# HoneyPI_Platine_2_0_BME680_280_Sensor_Bo.net
KiCad netlist of a schematic drawn in EAGLE
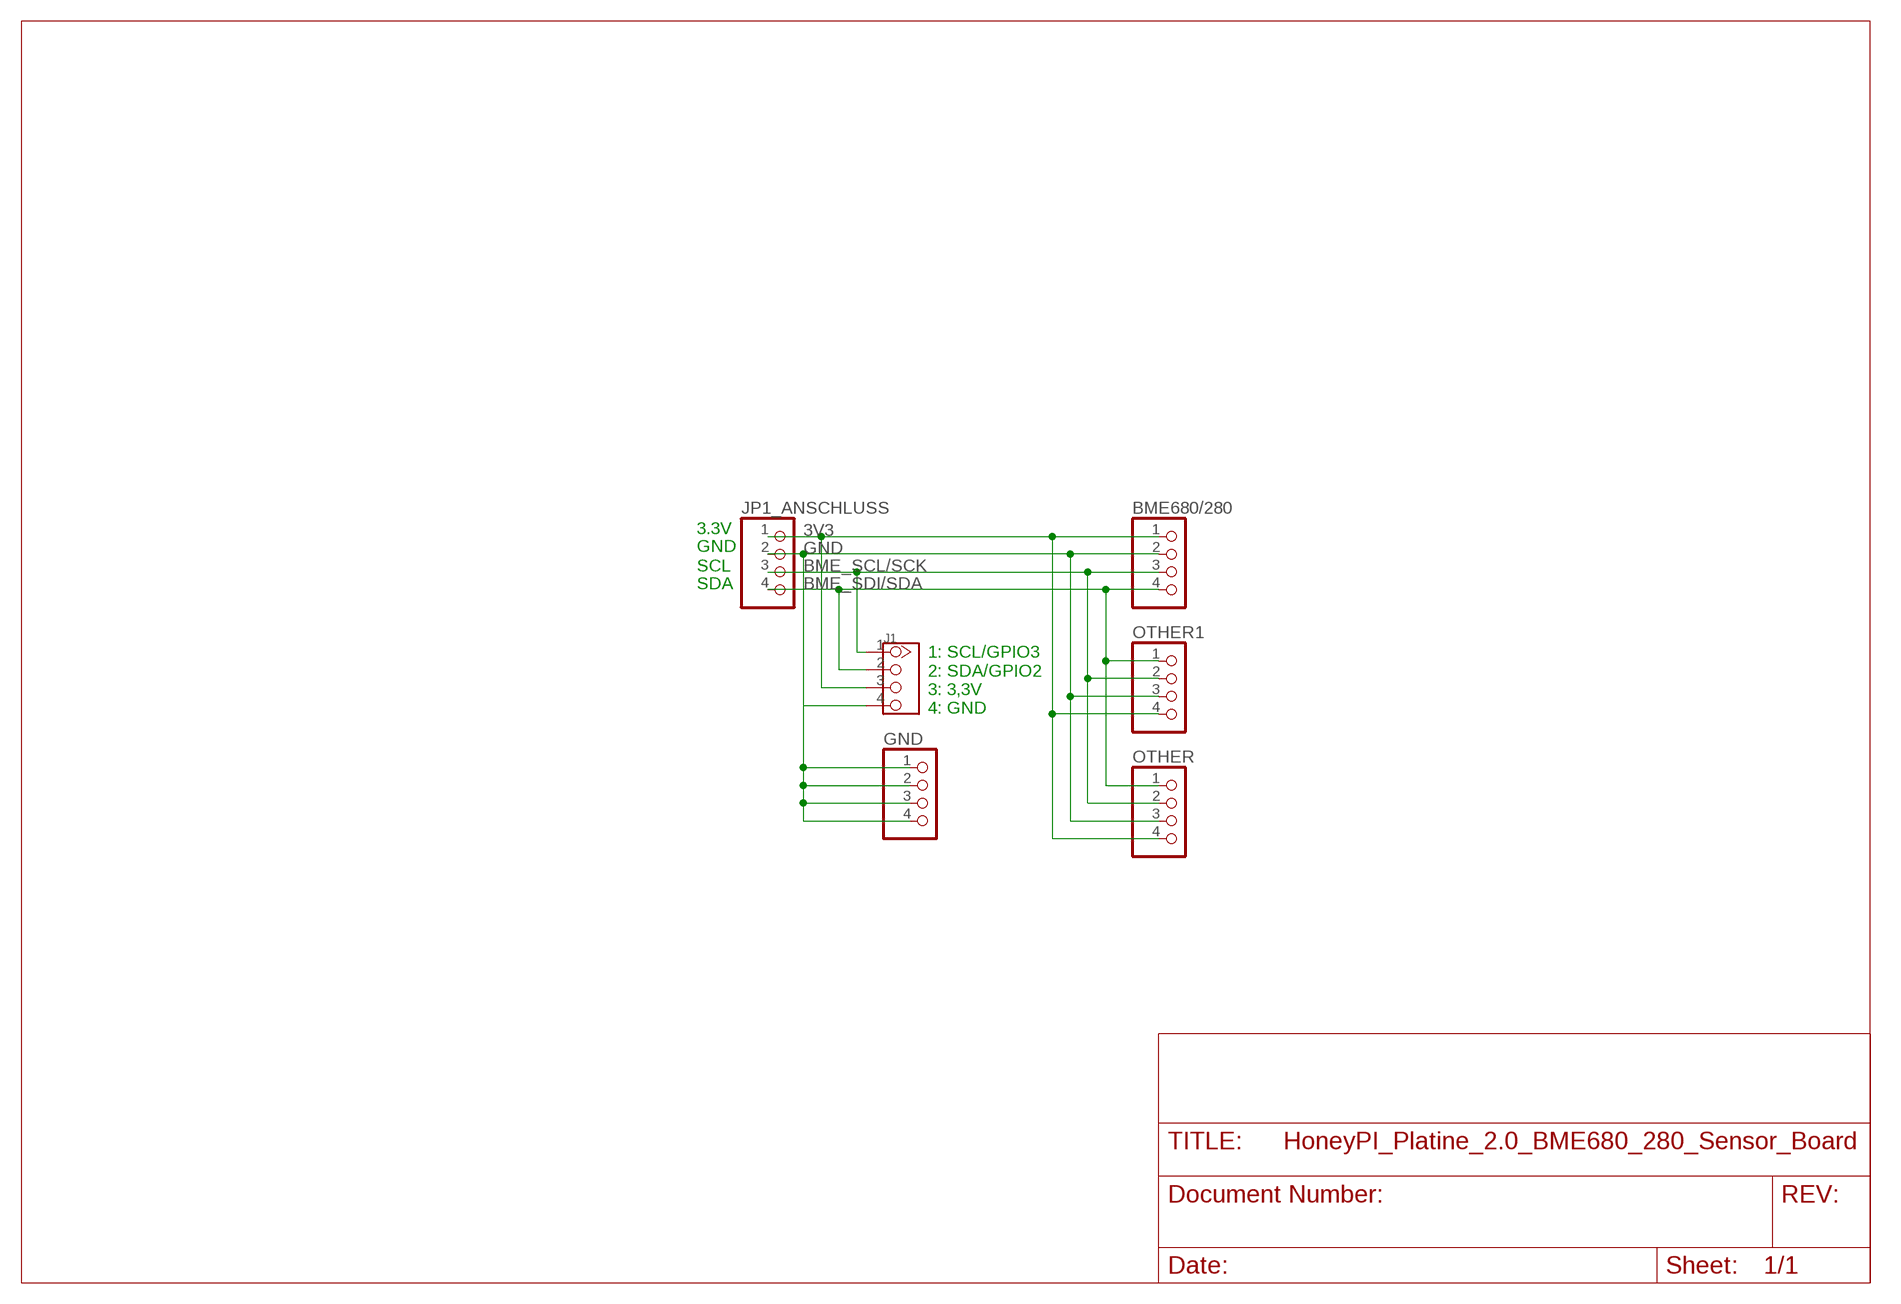
[diagram p0: schematic, sheet 1]

(export (version "E")
  (design (tool "Eeschema 10.0.6"))
  (components
    (comp (ref "BME680/280")
      (value "PINHD-1X4")
      (footprint "eagle-import:1X04")
      (libsource (lib "eagle-import") (part "PINHD-1X4"))
    )
    (comp (ref "GND")
      (value "PINHD-1X4")
      (footprint "eagle-import:1X04")
      (libsource (lib "eagle-import") (part "PINHD-1X4"))
    )
    (comp (ref "J1")
      (value "TWIG-4P-2.0-2.0")
      (footprint "eagle-import:4P-2.0")
      (libsource (lib "eagle-import") (part "TWIG-4P-2.0-2.0"))
    )
    (comp (ref "JP1_ANSCHLUSS")
      (value "PINHD-1X4")
      (footprint "eagle-import:1X04")
      (libsource (lib "eagle-import") (part "PINHD-1X4"))
    )
    (comp (ref "OTHER")
      (value "PINHD-1X4")
      (footprint "eagle-import:1X04")
      (libsource (lib "eagle-import") (part "PINHD-1X4"))
    )
    (comp (ref "OTHER1")
      (value "PINHD-1X4")
      (footprint "eagle-import:1X04")
      (libsource (lib "eagle-import") (part "PINHD-1X4"))
    )
  )
  (nets
    (net (code "1") (name "/3V3") (class "Default")
      (node (ref "BME680/280") (pin "1") (pinfunction "1_1") (pintype "passive"))
      (node (ref "J1") (pin "3") (pinfunction "3_3") (pintype "bidirectional"))
      (node (ref "JP1_ANSCHLUSS") (pin "1") (pinfunction "1_1") (pintype "passive"))
      (node (ref "OTHER") (pin "4") (pinfunction "4_4") (pintype "passive"))
      (node (ref "OTHER1") (pin "4") (pinfunction "4_4") (pintype "passive"))
    )
    (net (code "2") (name "/BME_SCL{slash}SCK") (class "Default")
      (node (ref "BME680/280") (pin "3") (pinfunction "3_3") (pintype "passive"))
      (node (ref "J1") (pin "1") (pinfunction "1_1") (pintype "bidirectional"))
      (node (ref "JP1_ANSCHLUSS") (pin "3") (pinfunction "3_3") (pintype "passive"))
      (node (ref "OTHER") (pin "2") (pinfunction "2_2") (pintype "passive"))
      (node (ref "OTHER1") (pin "2") (pinfunction "2_2") (pintype "passive"))
    )
    (net (code "3") (name "/BME_SDI{slash}SDA") (class "Default")
      (node (ref "BME680/280") (pin "4") (pinfunction "4_4") (pintype "passive"))
      (node (ref "J1") (pin "2") (pinfunction "2_2") (pintype "bidirectional"))
      (node (ref "JP1_ANSCHLUSS") (pin "4") (pinfunction "4_4") (pintype "passive"))
      (node (ref "OTHER") (pin "1") (pinfunction "1_1") (pintype "passive"))
      (node (ref "OTHER1") (pin "1") (pinfunction "1_1") (pintype "passive"))
    )
    (net (code "4") (name "/GND") (class "Default")
      (node (ref "BME680/280") (pin "2") (pinfunction "2_2") (pintype "passive"))
      (node (ref "GND") (pin "1") (pinfunction "1_1") (pintype "passive"))
      (node (ref "GND") (pin "2") (pinfunction "2_2") (pintype "passive"))
      (node (ref "GND") (pin "3") (pinfunction "3_3") (pintype "passive"))
      (node (ref "GND") (pin "4") (pinfunction "4_4") (pintype "passive"))
      (node (ref "J1") (pin "4") (pinfunction "4_4") (pintype "bidirectional"))
      (node (ref "JP1_ANSCHLUSS") (pin "2") (pinfunction "2_2") (pintype "passive"))
      (node (ref "OTHER") (pin "3") (pinfunction "3_3") (pintype "passive"))
      (node (ref "OTHER1") (pin "3") (pinfunction "3_3") (pintype "passive"))
    )
  )
)
